# SD_CARD.net
KiCad netlist of a schematic drawn in Altium Designer
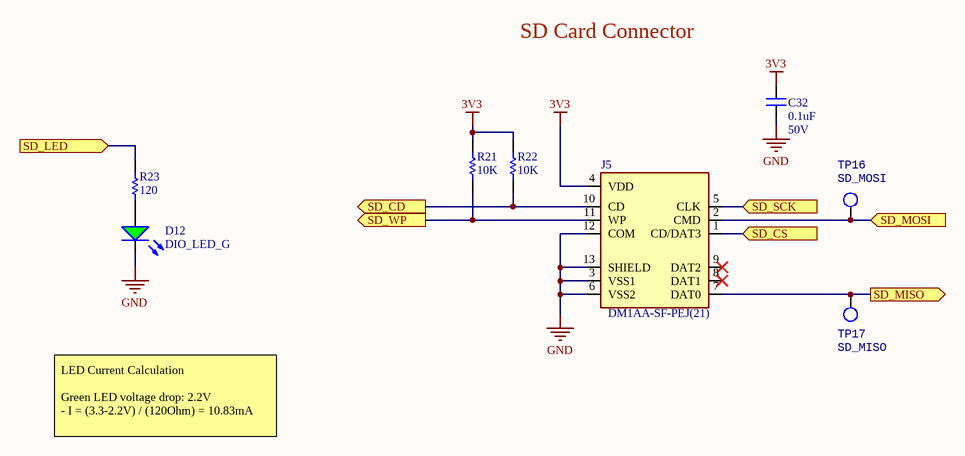
[diagram p0: SD_CARD.SchDoc]

(export (version "E")
  (design (tool "Eeschema 10.0.6"))
  (components
    (comp (ref "C32")
      (value "0.1uF")
      (footprint "CAPC2012X140N")
      (description "CAP CER 0.1UF 50V X7R 0805")
      (fields
        (field (name "TOLERANCE") "10%")
        (field (name "VOLTAGE RATING") "50V")
        (field (name "Comment") "CAP_0.1uF_50V_0805")
      )
      (libsource (lib "UWRT_Schematic_Library_2020") (part "CAP_0.1uF_50V_0805"))
    )
    (comp (ref "D12")
      (value "DIO_LED_G")
      (footprint "LED_0805_LINE")
      (description "LED GREEN DIFFUSED 0805 SMD")
      (libsource (lib "UWRT_Schematic_Library_2020") (part "DIO_LED_G"))
    )
    (comp (ref "J5")
      (value "SD_CARD_CON")
      (footprint "HRS_DM1AA-SF-PEJ(21)")
      (description "12 _9 + 3_ Position Card Connector Secure Digital - SD Surface Mount, Right Angle Gold")
      (fields (field (name "MANUFACTURER PART NUMBER 1") "DM1AA-SF-PEJ(21)"))
      (libsource (lib "UWRT_Schematic_Library_2020") (part "SD_CARD_CON"))
    )
    (comp (ref "R21")
      (value "10K")
      (footprint "RESC0603(1608)_N")
      (description "RES SMD 10K OHM 5% 1/10W 0603")
      (fields (field (name "TOLERANCE") "5%") (field (name "Comment") "RES_10K_0603"))
      (libsource (lib "UWRT_Schematic_Library_2020") (part "RES_10K_0603"))
    )
    (comp (ref "R22")
      (value "10K")
      (footprint "RESC0603(1608)_N")
      (description "RES SMD 10K OHM 5% 1/10W 0603")
      (fields (field (name "TOLERANCE") "5%") (field (name "Comment") "RES_10K_0603"))
      (libsource (lib "UWRT_Schematic_Library_2020") (part "RES_10K_0603"))
    )
    (comp (ref "R23")
      (value "120")
      (footprint "RESC0603(1608)_N")
      (description "RES SMD 120 OHM 5% 1/10W 0603")
      (fields (field (name "TOLERANCE") "5%") (field (name "Comment") "RES_120R_0603"))
      (libsource (lib "UWRT_Schematic_Library_2020") (part "RES_120R_0603"))
    )
    (comp (ref "TP16")
      (value "SD_MOSI")
      (footprint "TESTPOINT_LOOP")
      (description "Loop testpoint through-hole pad")
      (libsource (lib "UWRT_Schematic_Library_2020") (part "TESTPOINT_LOOP"))
    )
    (comp (ref "TP17")
      (value "SD_MISO")
      (footprint "TESTPOINT_LOOP")
      (description "Loop testpoint through-hole pad")
      (libsource (lib "UWRT_Schematic_Library_2020") (part "TESTPOINT_LOOP"))
    )
  )
  (nets
    (net (code "1") (name "/SD_CD") (class "Default")
      (node (ref "J5") (pin "10") (pinfunction "CD_10") (pintype "passive"))
      (node (ref "R22") (pin "1") (pinfunction "1_1") (pintype "passive"))
    )
    (net (code "2") (name "/SD_CS") (class "Default")
      (node (ref "J5") (pin "1") (pinfunction "CD/DAT3_1") (pintype "passive"))
    )
    (net (code "3") (name "/SD_LED") (class "Default")
      (node (ref "R23") (pin "1") (pinfunction "1_1") (pintype "passive"))
    )
    (net (code "4") (name "/SD_MISO") (class "Default")
      (node (ref "J5") (pin "7") (pinfunction "DAT0_7") (pintype "passive"))
      (node (ref "TP17") (pin "1") (pintype "passive"))
    )
    (net (code "5") (name "/SD_MOSI") (class "Default")
      (node (ref "J5") (pin "2") (pinfunction "CMD_2") (pintype "passive"))
      (node (ref "TP16") (pin "1") (pintype "passive"))
    )
    (net (code "6") (name "/SD_SCK") (class "Default")
      (node (ref "J5") (pin "5") (pinfunction "CLK_5") (pintype "passive"))
    )
    (net (code "7") (name "/SD_WP") (class "Default")
      (node (ref "J5") (pin "11") (pinfunction "WP_11") (pintype "passive"))
      (node (ref "R21") (pin "1") (pinfunction "1_1") (pintype "passive"))
    )
    (net (code "8") (name "3V3") (class "Default")
      (node (ref "C32") (pin "2") (pinfunction "2_2") (pintype "passive"))
      (node (ref "J5") (pin "4") (pinfunction "VDD_4") (pintype "power_in"))
      (node (ref "R21") (pin "2") (pinfunction "2_2") (pintype "passive"))
      (node (ref "R22") (pin "2") (pinfunction "2_2") (pintype "passive"))
    )
    (net (code "9") (name "GND") (class "Default")
      (node (ref "C32") (pin "1") (pinfunction "1_1") (pintype "passive"))
      (node (ref "D12") (pin "2") (pinfunction "K_2") (pintype "passive"))
      (node (ref "J5") (pin "12") (pinfunction "COM_12") (pintype "passive"))
      (node (ref "J5") (pin "13") (pinfunction "SHIELD_13") (pintype "passive"))
      (node (ref "J5") (pin "3") (pinfunction "VSS1_3") (pintype "power_in"))
      (node (ref "J5") (pin "6") (pinfunction "VSS2_6") (pintype "power_in"))
    )
    (net (code "10") (name "Net-(D12-A)") (class "Default")
      (node (ref "D12") (pin "1") (pinfunction "A_1") (pintype "passive"))
      (node (ref "R23") (pin "2") (pinfunction "2_2") (pintype "passive"))
    )
    (net (code "11") (name "unconnected-(J5-DAT1-Pad8)") (class "Default")
      (node (ref "J5") (pin "8") (pinfunction "DAT1_8") (pintype "passive+no_connect"))
    )
    (net (code "12") (name "unconnected-(J5-DAT2-Pad9)") (class "Default")
      (node (ref "J5") (pin "9") (pinfunction "DAT2_9") (pintype "passive+no_connect"))
    )
  )
)
